# TP_IHM_MAIN.net
KiCad netlist of a schematic drawn in Altium Designer
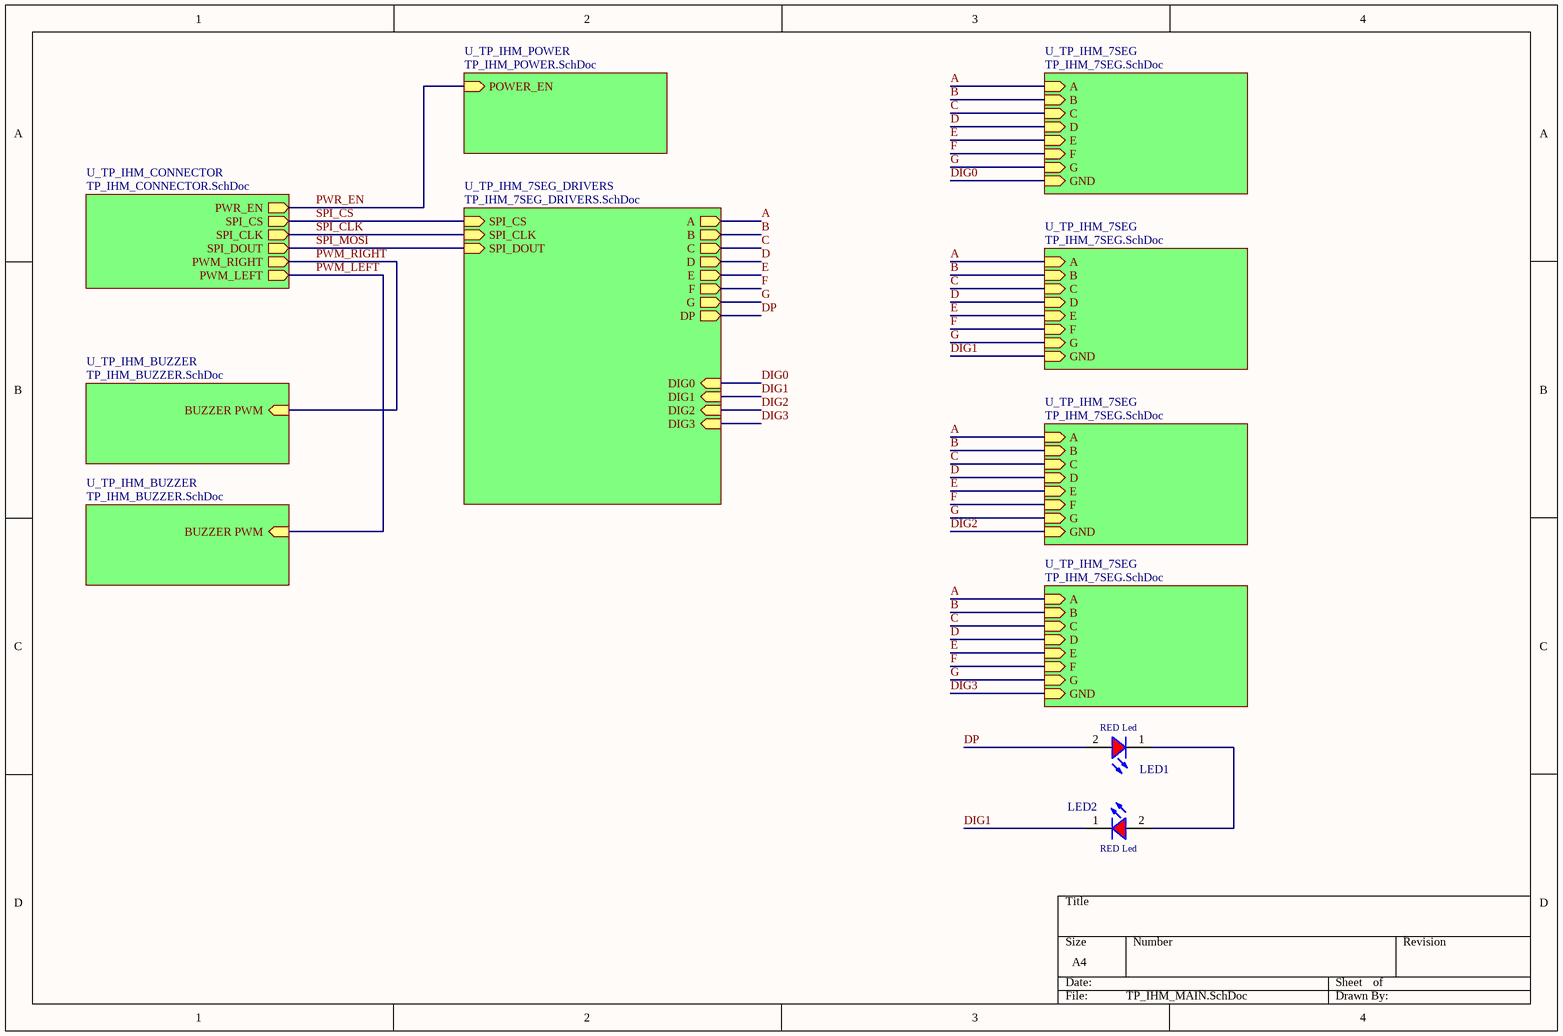
[diagram p0: TP_IHM_MAIN.SchDoc]

(export (version "E")
  (design (tool "Eeschema 10.0.6"))
  (components
    (comp (ref "LED1")
      (value "RED Led")
      (footprint "LED_0603_RED")
      (description "LED RED SMD WE 150060RS750x0")
      (libsource (lib "TpGiven") (part "LED_RED_SMD_WE_150060RS750x0"))
    )
    (comp (ref "LED2")
      (value "RED Led")
      (footprint "LED_0603_RED")
      (description "LED RED SMD WE 150060RS750x0")
      (libsource (lib "TpGiven") (part "LED_RED_SMD_WE_150060RS750x0"))
    )
  )
  (nets
    (net (code "6") (name "/DIG1") (class "Default")
      (node (ref "LED2") (pin "1") (pinfunction "K_1") (pintype "passive"))
    )
    (net (code "9") (name "/DP") (class "Default")
      (node (ref "LED1") (pin "2") (pinfunction "A_2") (pintype "passive"))
    )
    (net (code "19") (name "Net-(LED1-K)") (class "Default")
      (node (ref "LED1") (pin "1") (pinfunction "K_1") (pintype "passive"))
      (node (ref "LED2") (pin "2") (pinfunction "A_2") (pintype "passive"))
    )
  )
)
